# extension_board_v3.net
KiCad netlist of a schematic drawn in EAGLE
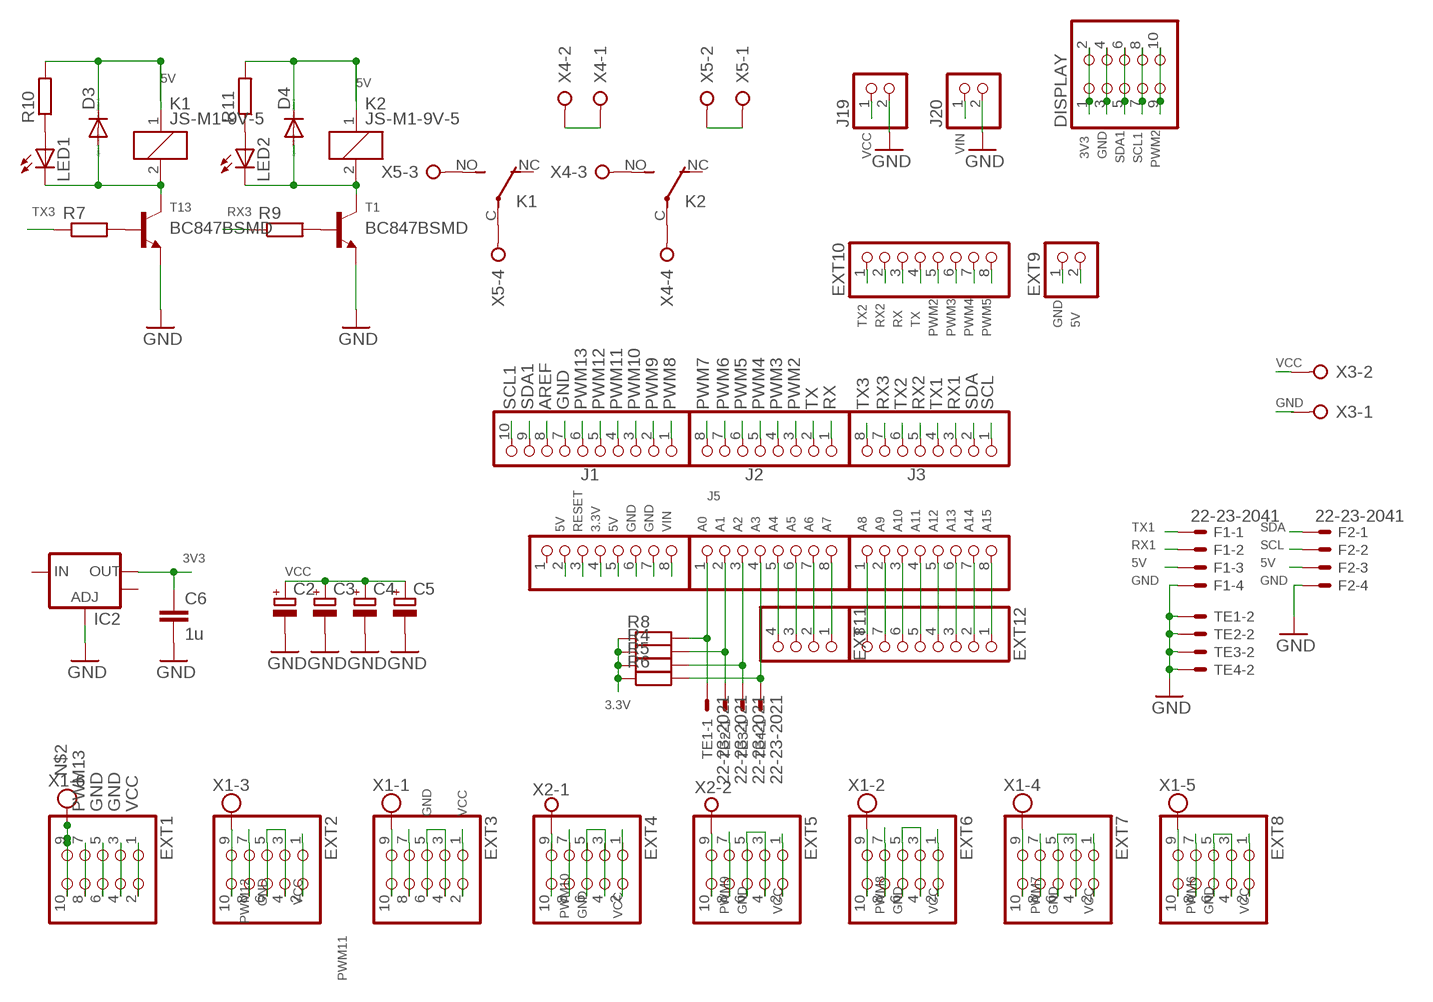
[diagram p0: schematic, sheet 1]

(export (version "E")
  (design (tool "Eeschema 10.0.6"))
  (components
    (comp (ref "C2")
      (value "CPOL-EUE2.5-7")
      (footprint "eagle-import:E2,5-7")
      (libsource (lib "eagle-import") (part "CPOL-EUE2.5-7"))
    )
    (comp (ref "C3")
      (value "CPOL-EUE2.5-7")
      (footprint "eagle-import:E2,5-7")
      (libsource (lib "eagle-import") (part "CPOL-EUE2.5-7"))
    )
    (comp (ref "C4")
      (value "CPOL-EUE2.5-7")
      (footprint "eagle-import:E2,5-7")
      (libsource (lib "eagle-import") (part "CPOL-EUE2.5-7"))
    )
    (comp (ref "C5")
      (value "CPOL-EUE2.5-7")
      (footprint "eagle-import:E2,5-7")
      (libsource (lib "eagle-import") (part "CPOL-EUE2.5-7"))
    )
    (comp (ref "C6")
      (value "1u")
      (footprint "eagle-import:C0805")
      (libsource (lib "eagle-import") (part "C-EUC0805"))
    )
    (comp (ref "D3")
      (value "DIODE-DO-214AC")
      (footprint "eagle-import:DO-214AC")
      (libsource (lib "eagle-import") (part "DIODE-DO-214AC"))
    )
    (comp (ref "D4")
      (value "DIODE-DO-214AC")
      (footprint "eagle-import:DO-214AC")
      (libsource (lib "eagle-import") (part "DIODE-DO-214AC"))
    )
    (comp (ref "DISPLAY")
      (value "PINHD-2X5")
      (footprint "eagle-import:2X05")
      (libsource (lib "eagle-import") (part "PINHD-2X5"))
    )
    (comp (ref "EXT1")
      (value "PINHD-2X5")
      (footprint "eagle-import:2X05")
      (libsource (lib "eagle-import") (part "PINHD-2X5"))
    )
    (comp (ref "EXT2")
      (value "PINHD-2X5")
      (footprint "eagle-import:2X05")
      (libsource (lib "eagle-import") (part "PINHD-2X5"))
    )
    (comp (ref "EXT3")
      (value "PINHD-2X5")
      (footprint "eagle-import:2X05")
      (libsource (lib "eagle-import") (part "PINHD-2X5"))
    )
    (comp (ref "EXT4")
      (value "PINHD-2X5")
      (footprint "eagle-import:2X05")
      (libsource (lib "eagle-import") (part "PINHD-2X5"))
    )
    (comp (ref "EXT5")
      (value "PINHD-2X5")
      (footprint "eagle-import:2X05")
      (libsource (lib "eagle-import") (part "PINHD-2X5"))
    )
    (comp (ref "EXT6")
      (value "PINHD-2X5")
      (footprint "eagle-import:2X05")
      (libsource (lib "eagle-import") (part "PINHD-2X5"))
    )
    (comp (ref "EXT7")
      (value "PINHD-2X5")
      (footprint "eagle-import:2X05")
      (libsource (lib "eagle-import") (part "PINHD-2X5"))
    )
    (comp (ref "EXT8")
      (value "PINHD-2X5")
      (footprint "eagle-import:2X05")
      (libsource (lib "eagle-import") (part "PINHD-2X5"))
    )
    (comp (ref "EXT9")
      (value "PINHD-1X2")
      (footprint "eagle-import:1X02")
      (libsource (lib "eagle-import") (part "PINHD-1X2"))
    )
    (comp (ref "EXT10")
      (value "PINHD-1X8")
      (footprint "eagle-import:1X08")
      (libsource (lib "eagle-import") (part "PINHD-1X8"))
    )
    (comp (ref "EXT11")
      (value "PINHD-1X4")
      (footprint "eagle-import:1X04")
      (libsource (lib "eagle-import") (part "PINHD-1X4"))
    )
    (comp (ref "EXT12")
      (value "PINHD-1X8")
      (footprint "eagle-import:1X08")
      (libsource (lib "eagle-import") (part "PINHD-1X8"))
    )
    (comp (ref "F1")
      (value "22-23-2041")
      (footprint "eagle-import:22-23-2041")
      (fields (field (name "MF") "MOLEX"))
      (libsource (lib "eagle-import") (part "22-23-2041"))
    )
    (comp (ref "F2")
      (value "22-23-2041")
      (footprint "eagle-import:22-23-2041")
      (fields (field (name "MF") "MOLEX"))
      (libsource (lib "eagle-import") (part "22-23-2041"))
    )
    (comp (ref "IC2")
      (value "V_REG_LM1117SOT223")
      (footprint "eagle-import:SOT223")
      (libsource (lib "eagle-import") (part "V_REG_LM1117SOT223"))
    )
    (comp (ref "J1")
      (value "PINHD-1X10")
      (footprint "eagle-import:1X10")
      (libsource (lib "eagle-import") (part "PINHD-1X10"))
    )
    (comp (ref "J2")
      (value "PINHD-1X8")
      (footprint "eagle-import:1X08")
      (libsource (lib "eagle-import") (part "PINHD-1X8"))
    )
    (comp (ref "J3")
      (value "PINHD-1X8")
      (footprint "eagle-import:1X08")
      (libsource (lib "eagle-import") (part "PINHD-1X8"))
    )
    (comp (ref "J4")
      (value "PINHD-1X8")
      (footprint "eagle-import:1X08")
      (libsource (lib "eagle-import") (part "PINHD-1X8"))
    )
    (comp (ref "J5")
      (value "PINHD-1X8")
      (footprint "eagle-import:1X08")
      (libsource (lib "eagle-import") (part "PINHD-1X8"))
    )
    (comp (ref "J6")
      (value "PINHD-1X8")
      (footprint "eagle-import:1X08")
      (libsource (lib "eagle-import") (part "PINHD-1X8"))
    )
    (comp (ref "J19")
      (value "PINHD-1X2")
      (footprint "eagle-import:1X02")
      (libsource (lib "eagle-import") (part "PINHD-1X2"))
    )
    (comp (ref "J20")
      (value "PINHD-1X2")
      (footprint "eagle-import:1X02")
      (libsource (lib "eagle-import") (part "PINHD-1X2"))
    )
    (comp (ref "K1")
      (value "JS-M1-9V-5")
      (footprint "eagle-import:JS-M")
      (libsource (lib "eagle-import") (part "JS-M1-9V-5"))
    )
    (comp (ref "K2")
      (value "JS-M1-9V-5")
      (footprint "eagle-import:JS-M")
      (libsource (lib "eagle-import") (part "JS-M1-9V-5"))
    )
    (comp (ref "LED1")
      (value "LEDSML1206")
      (footprint "eagle-import:SML1206")
      (libsource (lib "eagle-import") (part "LEDSML1206"))
    )
    (comp (ref "LED2")
      (value "LEDSML1206")
      (footprint "eagle-import:SML1206")
      (libsource (lib "eagle-import") (part "LEDSML1206"))
    )
    (comp (ref "R4")
      (value "R-EU_R1206")
      (footprint "eagle-import:R1206")
      (libsource (lib "eagle-import") (part "R-EU_R1206"))
    )
    (comp (ref "R5")
      (value "R-EU_R1206")
      (footprint "eagle-import:R1206")
      (libsource (lib "eagle-import") (part "R-EU_R1206"))
    )
    (comp (ref "R6")
      (value "R-EU_R1206")
      (footprint "eagle-import:R1206")
      (libsource (lib "eagle-import") (part "R-EU_R1206"))
    )
    (comp (ref "R7")
      (value "R-EU_R1206")
      (footprint "eagle-import:R1206")
      (libsource (lib "eagle-import") (part "R-EU_R1206"))
    )
    (comp (ref "R8")
      (value "R-EU_R1206")
      (footprint "eagle-import:R1206")
      (libsource (lib "eagle-import") (part "R-EU_R1206"))
    )
    (comp (ref "R9")
      (value "R-EU_R1206")
      (footprint "eagle-import:R1206")
      (libsource (lib "eagle-import") (part "R-EU_R1206"))
    )
    (comp (ref "R10")
      (value "R-EU_R1206")
      (footprint "eagle-import:R1206")
      (libsource (lib "eagle-import") (part "R-EU_R1206"))
    )
    (comp (ref "R11")
      (value "R-EU_R1206")
      (footprint "eagle-import:R1206")
      (libsource (lib "eagle-import") (part "R-EU_R1206"))
    )
    (comp (ref "T1")
      (value "BC847BSMD")
      (footprint "eagle-import:SOT23")
      (libsource (lib "eagle-import") (part "BC847SMDB"))
    )
    (comp (ref "T13")
      (value "BC847BSMD")
      (footprint "eagle-import:SOT23")
      (libsource (lib "eagle-import") (part "BC847SMDB"))
    )
    (comp (ref "TE1")
      (value "22-23-2021")
      (footprint "eagle-import:22-23-2021")
      (fields (field (name "MF") "MOLEX") (field (name "SPICEPREFIX") "X"))
      (libsource (lib "eagle-import") (part "22-23-2021"))
    )
    (comp (ref "TE2")
      (value "22-23-2021")
      (footprint "eagle-import:22-23-2021")
      (fields (field (name "MF") "MOLEX") (field (name "SPICEPREFIX") "X"))
      (libsource (lib "eagle-import") (part "22-23-2021"))
    )
    (comp (ref "TE3")
      (value "22-23-2021")
      (footprint "eagle-import:22-23-2021")
      (fields (field (name "MF") "MOLEX") (field (name "SPICEPREFIX") "X"))
      (libsource (lib "eagle-import") (part "22-23-2021"))
    )
    (comp (ref "TE4")
      (value "22-23-2021")
      (footprint "eagle-import:22-23-2021")
      (fields (field (name "MF") "MOLEX") (field (name "SPICEPREFIX") "X"))
      (libsource (lib "eagle-import") (part "22-23-2021"))
    )
    (comp (ref "X1")
      (value "W237-6")
      (footprint "eagle-import:W237-6")
      (libsource (lib "eagle-import") (part "W237-6"))
    )
    (comp (ref "X2")
      (value "W237-02P")
      (footprint "eagle-import:W237-132")
      (libsource (lib "eagle-import") (part "W237-02P"))
    )
    (comp (ref "X3")
      (value "W237-02P")
      (footprint "eagle-import:W237-132")
      (libsource (lib "eagle-import") (part "W237-02P"))
    )
    (comp (ref "X4")
      (value "W237-04P")
      (footprint "eagle-import:W237-4P")
      (libsource (lib "eagle-import") (part "W237-04P"))
    )
    (comp (ref "X5")
      (value "W237-04P")
      (footprint "eagle-import:W237-4P")
      (libsource (lib "eagle-import") (part "W237-04P"))
    )
  )
  (nets
    (net (code "1") (name "/3.3V") (class "Default")
      (node (ref "J6") (pin "4") (pinfunction "4_4") (pintype "passive"))
      (node (ref "R4") (pin "1") (pinfunction "1_1") (pintype "passive"))
      (node (ref "R5") (pin "1") (pinfunction "1_1") (pintype "passive"))
      (node (ref "R6") (pin "1") (pinfunction "1_1") (pintype "passive"))
      (node (ref "R8") (pin "1") (pinfunction "1_1") (pintype "passive"))
    )
    (net (code "2") (name "/3V3") (class "Default")
      (node (ref "C6") (pin "1") (pinfunction "1_1") (pintype "passive"))
      (node (ref "DISPLAY") (pin "1") (pinfunction "1_1") (pintype "passive"))
      (node (ref "DISPLAY") (pin "2") (pinfunction "2_2") (pintype "passive"))
      (node (ref "IC2") (pin "2") (pinfunction "OUT_2") (pintype "output"))
    )
    (net (code "3") (name "/5V") (class "Default")
      (node (ref "D3") (pin "C") (pinfunction "C_C") (pintype "passive"))
      (node (ref "D4") (pin "C") (pinfunction "C_C") (pintype "passive"))
      (node (ref "EXT9") (pin "2") (pinfunction "2_2") (pintype "passive"))
      (node (ref "F1") (pin "3") (pinfunction "S_3") (pintype "passive"))
      (node (ref "F2") (pin "3") (pinfunction "S_3") (pintype "passive"))
      (node (ref "J6") (pin "2") (pinfunction "2_2") (pintype "passive"))
      (node (ref "J6") (pin "5") (pinfunction "5_5") (pintype "passive"))
      (node (ref "K1") (pin "1") (pinfunction "1_1") (pintype "passive"))
      (node (ref "K2") (pin "1") (pinfunction "1_1") (pintype "passive"))
      (node (ref "R10") (pin "2") (pinfunction "2_2") (pintype "passive"))
      (node (ref "R11") (pin "2") (pinfunction "2_2") (pintype "passive"))
    )
    (net (code "4") (name "/A0") (class "Default")
      (node (ref "J5") (pin "1") (pinfunction "1_1") (pintype "passive"))
      (node (ref "R8") (pin "2") (pinfunction "2_2") (pintype "passive"))
      (node (ref "TE1") (pin "1") (pinfunction "S_1") (pintype "passive"))
    )
    (net (code "5") (name "/A1") (class "Default")
      (node (ref "J5") (pin "2") (pinfunction "2_2") (pintype "passive"))
      (node (ref "R4") (pin "2") (pinfunction "2_2") (pintype "passive"))
      (node (ref "TE2") (pin "1") (pinfunction "S_1") (pintype "passive"))
    )
    (net (code "6") (name "/A2") (class "Default")
      (node (ref "J5") (pin "3") (pinfunction "3_3") (pintype "passive"))
      (node (ref "R5") (pin "2") (pinfunction "2_2") (pintype "passive"))
      (node (ref "TE3") (pin "1") (pinfunction "S_1") (pintype "passive"))
    )
    (net (code "7") (name "/A3") (class "Default")
      (node (ref "J5") (pin "4") (pinfunction "4_4") (pintype "passive"))
      (node (ref "R6") (pin "2") (pinfunction "2_2") (pintype "passive"))
      (node (ref "TE4") (pin "1") (pinfunction "S_1") (pintype "passive"))
    )
    (net (code "8") (name "/A4") (class "Default")
      (node (ref "EXT11") (pin "4") (pinfunction "4_4") (pintype "passive"))
      (node (ref "J5") (pin "5") (pinfunction "5_5") (pintype "passive"))
    )
    (net (code "9") (name "/A5") (class "Default")
      (node (ref "EXT11") (pin "3") (pinfunction "3_3") (pintype "passive"))
      (node (ref "J5") (pin "6") (pinfunction "6_6") (pintype "passive"))
    )
    (net (code "10") (name "/A6") (class "Default")
      (node (ref "EXT11") (pin "2") (pinfunction "2_2") (pintype "passive"))
      (node (ref "J5") (pin "7") (pinfunction "7_7") (pintype "passive"))
    )
    (net (code "11") (name "/A7") (class "Default")
      (node (ref "EXT11") (pin "1") (pinfunction "1_1") (pintype "passive"))
      (node (ref "J5") (pin "8") (pinfunction "8_8") (pintype "passive"))
    )
    (net (code "12") (name "/A8") (class "Default")
      (node (ref "EXT12") (pin "8") (pinfunction "8_8") (pintype "passive"))
      (node (ref "J4") (pin "1") (pinfunction "1_1") (pintype "passive"))
    )
    (net (code "13") (name "/A9") (class "Default")
      (node (ref "EXT12") (pin "7") (pinfunction "7_7") (pintype "passive"))
      (node (ref "J4") (pin "2") (pinfunction "2_2") (pintype "passive"))
    )
    (net (code "14") (name "/A10") (class "Default")
      (node (ref "EXT12") (pin "6") (pinfunction "6_6") (pintype "passive"))
      (node (ref "J4") (pin "3") (pinfunction "3_3") (pintype "passive"))
    )
    (net (code "15") (name "/A11") (class "Default")
      (node (ref "EXT12") (pin "5") (pinfunction "5_5") (pintype "passive"))
      (node (ref "J4") (pin "4") (pinfunction "4_4") (pintype "passive"))
    )
    (net (code "16") (name "/A12") (class "Default")
      (node (ref "EXT12") (pin "4") (pinfunction "4_4") (pintype "passive"))
      (node (ref "J4") (pin "5") (pinfunction "5_5") (pintype "passive"))
    )
    (net (code "17") (name "/A13") (class "Default")
      (node (ref "EXT12") (pin "3") (pinfunction "3_3") (pintype "passive"))
      (node (ref "J4") (pin "6") (pinfunction "6_6") (pintype "passive"))
    )
    (net (code "18") (name "/A14") (class "Default")
      (node (ref "EXT12") (pin "2") (pinfunction "2_2") (pintype "passive"))
      (node (ref "J4") (pin "7") (pinfunction "7_7") (pintype "passive"))
    )
    (net (code "19") (name "/A15") (class "Default")
      (node (ref "EXT12") (pin "1") (pinfunction "1_1") (pintype "passive"))
      (node (ref "J4") (pin "8") (pinfunction "8_8") (pintype "passive"))
    )
    (net (code "20") (name "/AREF") (class "Default")
      (node (ref "J1") (pin "8") (pinfunction "8_8") (pintype "passive"))
    )
    (net (code "21") (name "/N$2") (class "Default")
      (node (ref "EXT1") (pin "10") (pinfunction "10_10") (pintype "passive"))
      (node (ref "EXT1") (pin "9") (pinfunction "9_9") (pintype "passive"))
      (node (ref "X1") (pin "6") (pinfunction "KL_6") (pintype "passive"))
    )
    (net (code "22") (name "/PWM2") (class "Default")
      (node (ref "DISPLAY") (pin "10") (pinfunction "10_10") (pintype "passive"))
      (node (ref "DISPLAY") (pin "9") (pinfunction "9_9") (pintype "passive"))
      (node (ref "EXT10") (pin "5") (pinfunction "5_5") (pintype "passive"))
      (node (ref "J2") (pin "3") (pinfunction "3_3") (pintype "passive"))
    )
    (net (code "23") (name "/PWM3") (class "Default")
      (node (ref "EXT10") (pin "6") (pinfunction "6_6") (pintype "passive"))
      (node (ref "J2") (pin "4") (pinfunction "4_4") (pintype "passive"))
    )
    (net (code "24") (name "/PWM4") (class "Default")
      (node (ref "EXT10") (pin "7") (pinfunction "7_7") (pintype "passive"))
      (node (ref "J2") (pin "5") (pinfunction "5_5") (pintype "passive"))
    )
    (net (code "25") (name "/PWM5") (class "Default")
      (node (ref "EXT10") (pin "8") (pinfunction "8_8") (pintype "passive"))
      (node (ref "J2") (pin "6") (pinfunction "6_6") (pintype "passive"))
    )
    (net (code "26") (name "/PWM6") (class "Default")
      (node (ref "EXT8") (pin "7") (pinfunction "7_7") (pintype "passive"))
      (node (ref "EXT8") (pin "8") (pinfunction "8_8") (pintype "passive"))
      (node (ref "J2") (pin "7") (pinfunction "7_7") (pintype "passive"))
    )
    (net (code "27") (name "/PWM7") (class "Default")
      (node (ref "EXT7") (pin "7") (pinfunction "7_7") (pintype "passive"))
      (node (ref "EXT7") (pin "8") (pinfunction "8_8") (pintype "passive"))
      (node (ref "J2") (pin "8") (pinfunction "8_8") (pintype "passive"))
    )
    (net (code "28") (name "/PWM8") (class "Default")
      (node (ref "EXT6") (pin "7") (pinfunction "7_7") (pintype "passive"))
      (node (ref "EXT6") (pin "8") (pinfunction "8_8") (pintype "passive"))
      (node (ref "J1") (pin "1") (pinfunction "1_1") (pintype "passive"))
    )
    (net (code "29") (name "/PWM9") (class "Default")
      (node (ref "EXT5") (pin "7") (pinfunction "7_7") (pintype "passive"))
      (node (ref "EXT5") (pin "8") (pinfunction "8_8") (pintype "passive"))
      (node (ref "J1") (pin "2") (pinfunction "2_2") (pintype "passive"))
    )
    (net (code "30") (name "/PWM10") (class "Default")
      (node (ref "EXT4") (pin "7") (pinfunction "7_7") (pintype "passive"))
      (node (ref "EXT4") (pin "8") (pinfunction "8_8") (pintype "passive"))
      (node (ref "J1") (pin "3") (pinfunction "3_3") (pintype "passive"))
    )
    (net (code "31") (name "/PWM11") (class "Default")
      (node (ref "EXT3") (pin "7") (pinfunction "7_7") (pintype "passive"))
      (node (ref "EXT3") (pin "8") (pinfunction "8_8") (pintype "passive"))
      (node (ref "J1") (pin "4") (pinfunction "4_4") (pintype "passive"))
    )
    (net (code "32") (name "/PWM12") (class "Default")
      (node (ref "EXT2") (pin "7") (pinfunction "7_7") (pintype "passive"))
      (node (ref "EXT2") (pin "8") (pinfunction "8_8") (pintype "passive"))
      (node (ref "J1") (pin "5") (pinfunction "5_5") (pintype "passive"))
    )
    (net (code "33") (name "/PWM13") (class "Default")
      (node (ref "EXT1") (pin "7") (pinfunction "7_7") (pintype "passive"))
      (node (ref "EXT1") (pin "8") (pinfunction "8_8") (pintype "passive"))
      (node (ref "J1") (pin "6") (pinfunction "6_6") (pintype "passive"))
    )
    (net (code "34") (name "/RESET") (class "Default")
      (node (ref "J6") (pin "3") (pinfunction "3_3") (pintype "passive"))
    )
    (net (code "35") (name "/RX") (class "Default")
      (node (ref "EXT10") (pin "3") (pinfunction "3_3") (pintype "passive"))
      (node (ref "J2") (pin "1") (pinfunction "1_1") (pintype "passive"))
    )
    (net (code "36") (name "/RX1") (class "Default")
      (node (ref "F1") (pin "2") (pinfunction "S_2") (pintype "passive"))
      (node (ref "J3") (pin "3") (pinfunction "3_3") (pintype "passive"))
    )
    (net (code "37") (name "/RX2") (class "Default")
      (node (ref "EXT10") (pin "2") (pinfunction "2_2") (pintype "passive"))
      (node (ref "J3") (pin "5") (pinfunction "5_5") (pintype "passive"))
    )
    (net (code "38") (name "/RX3") (class "Default")
      (node (ref "J3") (pin "7") (pinfunction "7_7") (pintype "passive"))
      (node (ref "R9") (pin "1") (pinfunction "1_1") (pintype "passive"))
    )
    (net (code "39") (name "/SCL") (class "Default")
      (node (ref "F2") (pin "2") (pinfunction "S_2") (pintype "passive"))
      (node (ref "J3") (pin "1") (pinfunction "1_1") (pintype "passive"))
    )
    (net (code "40") (name "/SCL1") (class "Default")
      (node (ref "DISPLAY") (pin "7") (pinfunction "7_7") (pintype "passive"))
      (node (ref "DISPLAY") (pin "8") (pinfunction "8_8") (pintype "passive"))
      (node (ref "J1") (pin "10") (pinfunction "10_10") (pintype "passive"))
    )
    (net (code "41") (name "/SDA") (class "Default")
      (node (ref "F2") (pin "1") (pinfunction "S_1") (pintype "passive"))
      (node (ref "J3") (pin "2") (pinfunction "2_2") (pintype "passive"))
    )
    (net (code "42") (name "/SDA1") (class "Default")
      (node (ref "DISPLAY") (pin "5") (pinfunction "5_5") (pintype "passive"))
      (node (ref "DISPLAY") (pin "6") (pinfunction "6_6") (pintype "passive"))
      (node (ref "J1") (pin "9") (pinfunction "9_9") (pintype "passive"))
    )
    (net (code "43") (name "/TX") (class "Default")
      (node (ref "EXT10") (pin "4") (pinfunction "4_4") (pintype "passive"))
      (node (ref "J2") (pin "2") (pinfunction "2_2") (pintype "passive"))
    )
    (net (code "44") (name "/TX1") (class "Default")
      (node (ref "F1") (pin "1") (pinfunction "S_1") (pintype "passive"))
      (node (ref "J3") (pin "4") (pinfunction "4_4") (pintype "passive"))
    )
    (net (code "45") (name "/TX2") (class "Default")
      (node (ref "EXT10") (pin "1") (pinfunction "1_1") (pintype "passive"))
      (node (ref "J3") (pin "6") (pinfunction "6_6") (pintype "passive"))
    )
    (net (code "46") (name "/TX3") (class "Default")
      (node (ref "J3") (pin "8") (pinfunction "8_8") (pintype "passive"))
      (node (ref "R7") (pin "1") (pinfunction "1_1") (pintype "passive"))
    )
    (net (code "47") (name "/VCC") (class "Default")
      (node (ref "C2") (pin "+") (pinfunction "+_+") (pintype "passive"))
      (node (ref "C3") (pin "+") (pinfunction "+_+") (pintype "passive"))
      (node (ref "C4") (pin "+") (pinfunction "+_+") (pintype "passive"))
      (node (ref "C5") (pin "+") (pinfunction "+_+") (pintype "passive"))
      (node (ref "EXT1") (pin "1") (pinfunction "1_1") (pintype "passive"))
      (node (ref "EXT1") (pin "2") (pinfunction "2_2") (pintype "passive"))
      (node (ref "EXT2") (pin "1") (pinfunction "1_1") (pintype "passive"))
      (node (ref "EXT2") (pin "2") (pinfunction "2_2") (pintype "passive"))
      (node (ref "EXT3") (pin "1") (pinfunction "1_1") (pintype "passive"))
      (node (ref "EXT3") (pin "2") (pinfunction "2_2") (pintype "passive"))
      (node (ref "EXT4") (pin "1") (pinfunction "1_1") (pintype "passive"))
      (node (ref "EXT4") (pin "2") (pinfunction "2_2") (pintype "passive"))
      (node (ref "EXT5") (pin "1") (pinfunction "1_1") (pintype "passive"))
      (node (ref "EXT5") (pin "2") (pinfunction "2_2") (pintype "passive"))
      (node (ref "EXT6") (pin "1") (pinfunction "1_1") (pintype "passive"))
      (node (ref "EXT6") (pin "2") (pinfunction "2_2") (pintype "passive"))
      (node (ref "EXT7") (pin "1") (pinfunction "1_1") (pintype "passive"))
      (node (ref "EXT7") (pin "2") (pinfunction "2_2") (pintype "passive"))
      (node (ref "EXT8") (pin "1") (pinfunction "1_1") (pintype "passive"))
      (node (ref "EXT8") (pin "2") (pinfunction "2_2") (pintype "passive"))
      (node (ref "J19") (pin "1") (pinfunction "1_1") (pintype "passive"))
      (node (ref "X3") (pin "2") (pinfunction "KL_2") (pintype "passive"))
    )
    (net (code "48") (name "/VIN") (class "Default")
      (node (ref "J20") (pin "1") (pinfunction "1_1") (pintype "passive"))
      (node (ref "J6") (pin "8") (pinfunction "8_8") (pintype "passive"))
    )
    (net (code "49") (name "GND") (class "Default")
      (node (ref "C2") (pin "-") (pinfunction "-_-") (pintype "passive"))
      (node (ref "C3") (pin "-") (pinfunction "-_-") (pintype "passive"))
      (node (ref "C4") (pin "-") (pinfunction "-_-") (pintype "passive"))
      (node (ref "C5") (pin "-") (pinfunction "-_-") (pintype "passive"))
      (node (ref "C6") (pin "2") (pinfunction "2_2") (pintype "passive"))
      (node (ref "DISPLAY") (pin "3") (pinfunction "3_3") (pintype "passive"))
      (node (ref "DISPLAY") (pin "4") (pinfunction "4_4") (pintype "passive"))
      (node (ref "EXT1") (pin "3") (pinfunction "3_3") (pintype "passive"))
      (node (ref "EXT1") (pin "4") (pinfunction "4_4") (pintype "passive"))
      (node (ref "EXT1") (pin "5") (pinfunction "5_5") (pintype "passive"))
      (node (ref "EXT1") (pin "6") (pinfunction "6_6") (pintype "passive"))
      (node (ref "EXT2") (pin "3") (pinfunction "3_3") (pintype "passive"))
      (node (ref "EXT2") (pin "4") (pinfunction "4_4") (pintype "passive"))
      (node (ref "EXT2") (pin "5") (pinfunction "5_5") (pintype "passive"))
      (node (ref "EXT2") (pin "6") (pinfunction "6_6") (pintype "passive"))
      (node (ref "EXT3") (pin "3") (pinfunction "3_3") (pintype "passive"))
      (node (ref "EXT3") (pin "4") (pinfunction "4_4") (pintype "passive"))
      (node (ref "EXT3") (pin "5") (pinfunction "5_5") (pintype "passive"))
      (node (ref "EXT3") (pin "6") (pinfunction "6_6") (pintype "passive"))
      (node (ref "EXT4") (pin "3") (pinfunction "3_3") (pintype "passive"))
      (node (ref "EXT4") (pin "4") (pinfunction "4_4") (pintype "passive"))
      (node (ref "EXT4") (pin "5") (pinfunction "5_5") (pintype "passive"))
      (node (ref "EXT4") (pin "6") (pinfunction "6_6") (pintype "passive"))
      (node (ref "EXT5") (pin "3") (pinfunction "3_3") (pintype "passive"))
      (node (ref "EXT5") (pin "4") (pinfunction "4_4") (pintype "passive"))
      (node (ref "EXT5") (pin "5") (pinfunction "5_5") (pintype "passive"))
      (node (ref "EXT5") (pin "6") (pinfunction "6_6") (pintype "passive"))
      (node (ref "EXT6") (pin "3") (pinfunction "3_3") (pintype "passive"))
      (node (ref "EXT6") (pin "4") (pinfunction "4_4") (pintype "passive"))
      (node (ref "EXT6") (pin "5") (pinfunction "5_5") (pintype "passive"))
      (node (ref "EXT6") (pin "6") (pinfunction "6_6") (pintype "passive"))
      (node (ref "EXT7") (pin "3") (pinfunction "3_3") (pintype "passive"))
      (node (ref "EXT7") (pin "4") (pinfunction "4_4") (pintype "passive"))
      (node (ref "EXT7") (pin "5") (pinfunction "5_5") (pintype "passive"))
      (node (ref "EXT7") (pin "6") (pinfunction "6_6") (pintype "passive"))
      (node (ref "EXT8") (pin "3") (pinfunction "3_3") (pintype "passive"))
      (node (ref "EXT8") (pin "4") (pinfunction "4_4") (pintype "passive"))
      (node (ref "EXT8") (pin "5") (pinfunction "5_5") (pintype "passive"))
      (node (ref "EXT8") (pin "6") (pinfunction "6_6") (pintype "passive"))
      (node (ref "EXT9") (pin "1") (pinfunction "1_1") (pintype "passive"))
      (node (ref "F1") (pin "4") (pinfunction "S_4") (pintype "passive"))
      (node (ref "F2") (pin "4") (pinfunction "S_4") (pintype "passive"))
      (node (ref "IC2") (pin "1") (pinfunction "ADJ_1") (pintype "input"))
      (node (ref "J1") (pin "7") (pinfunction "7_7") (pintype "passive"))
      (node (ref "J19") (pin "2") (pinfunction "2_2") (pintype "passive"))
      (node (ref "J20") (pin "2") (pinfunction "2_2") (pintype "passive"))
      (node (ref "J6") (pin "6") (pinfunction "6_6") (pintype "passive"))
      (node (ref "J6") (pin "7") (pinfunction "7_7") (pintype "passive"))
      (node (ref "T1") (pin "2") (pinfunction "E_2") (pintype "passive"))
      (node (ref "T13") (pin "2") (pinfunction "E_2") (pintype "passive"))
      (node (ref "TE1") (pin "2") (pinfunction "S_2") (pintype "passive"))
      (node (ref "TE2") (pin "2") (pinfunction "S_2") (pintype "passive"))
      (node (ref "TE3") (pin "2") (pinfunction "S_2") (pintype "passive"))
      (node (ref "TE4") (pin "2") (pinfunction "S_2") (pintype "passive"))
      (node (ref "X3") (pin "1") (pinfunction "KL_1") (pintype "passive"))
    )
    (net (code "50") (name "Net-(K1B-P)") (class "Default")
      (node (ref "K1") (pin "C") (pinfunction "P_C") (pintype "passive"))
      (node (ref "X5") (pin "4") (pinfunction "KL_4") (pintype "passive"))
    )
    (net (code "51") (name "Net-(K1B-S)") (class "Default")
      (node (ref "K1") (pin "NO") (pinfunction "S_NO") (pintype "passive"))
      (node (ref "X5") (pin "3") (pinfunction "KL_3") (pintype "passive"))
    )
    (net (code "52") (name "Net-(K2B-P)") (class "Default")
      (node (ref "K2") (pin "C") (pinfunction "P_C") (pintype "passive"))
      (node (ref "X4") (pin "4") (pinfunction "KL_4") (pintype "passive"))
    )
    (net (code "53") (name "Net-(K2B-S)") (class "Default")
      (node (ref "K2") (pin "NO") (pinfunction "S_NO") (pintype "passive"))
      (node (ref "X4") (pin "3") (pinfunction "KL_3") (pintype "passive"))
    )
    (net (code "54") (name "Net-(LED1-PadA)") (class "Default")
      (node (ref "LED1") (pin "A") (pinfunction "A_A") (pintype "passive"))
      (node (ref "R10") (pin "1") (pinfunction "1_1") (pintype "passive"))
    )
    (net (code "55") (name "Net-(LED2-PadA)") (class "Default")
      (node (ref "LED2") (pin "A") (pinfunction "A_A") (pintype "passive"))
      (node (ref "R11") (pin "1") (pinfunction "1_1") (pintype "passive"))
    )
    (net (code "56") (name "Net-(T1-B)") (class "Default")
      (node (ref "R9") (pin "2") (pinfunction "2_2") (pintype "passive"))
      (node (ref "T1") (pin "1") (pinfunction "B_1") (pintype "passive"))
    )
    (net (code "57") (name "Net-(T1-C)") (class "Default")
      (node (ref "D4") (pin "A") (pinfunction "A_A") (pintype "passive"))
      (node (ref "K2") (pin "2") (pinfunction "2_2") (pintype "passive"))
      (node (ref "LED2") (pin "C") (pinfunction "C_C") (pintype "passive"))
      (node (ref "T1") (pin "3") (pinfunction "C_3") (pintype "passive"))
    )
    (net (code "58") (name "Net-(T13-B)") (class "Default")
      (node (ref "R7") (pin "2") (pinfunction "2_2") (pintype "passive"))
      (node (ref "T13") (pin "1") (pinfunction "B_1") (pintype "passive"))
    )
    (net (code "59") (name "Net-(T13-C)") (class "Default")
      (node (ref "D3") (pin "A") (pinfunction "A_A") (pintype "passive"))
      (node (ref "K1") (pin "2") (pinfunction "2_2") (pintype "passive"))
      (node (ref "LED1") (pin "C") (pinfunction "C_C") (pintype "passive"))
      (node (ref "T13") (pin "3") (pinfunction "C_3") (pintype "passive"))
    )
    (net (code "60") (name "Net-(X1A-KL)") (class "Default")
      (node (ref "EXT3") (pin "10") (pinfunction "10_10") (pintype "passive"))
      (node (ref "EXT3") (pin "9") (pinfunction "9_9") (pintype "passive"))
      (node (ref "X1") (pin "1") (pinfunction "KL_1") (pintype "passive"))
    )
    (net (code "61") (name "Net-(X1B-KL)") (class "Default")
      (node (ref "EXT6") (pin "10") (pinfunction "10_10") (pintype "passive"))
      (node (ref "EXT6") (pin "9") (pinfunction "9_9") (pintype "passive"))
      (node (ref "X1") (pin "2") (pinfunction "KL_2") (pintype "passive"))
    )
    (net (code "62") (name "Net-(X1C-KL)") (class "Default")
      (node (ref "EXT2") (pin "10") (pinfunction "10_10") (pintype "passive"))
      (node (ref "EXT2") (pin "9") (pinfunction "9_9") (pintype "passive"))
      (node (ref "X1") (pin "3") (pinfunction "KL_3") (pintype "passive"))
    )
    (net (code "63") (name "Net-(X1D-KL)") (class "Default")
      (node (ref "EXT7") (pin "10") (pinfunction "10_10") (pintype "passive"))
      (node (ref "EXT7") (pin "9") (pinfunction "9_9") (pintype "passive"))
      (node (ref "X1") (pin "4") (pinfunction "KL_4") (pintype "passive"))
    )
    (net (code "64") (name "Net-(X1E-KL)") (class "Default")
      (node (ref "EXT8") (pin "10") (pinfunction "10_10") (pintype "passive"))
      (node (ref "EXT8") (pin "9") (pinfunction "9_9") (pintype "passive"))
      (node (ref "X1") (pin "5") (pinfunction "KL_5") (pintype "passive"))
    )
    (net (code "65") (name "Net-(X2A-KL)") (class "Default")
      (node (ref "EXT4") (pin "10") (pinfunction "10_10") (pintype "passive"))
      (node (ref "EXT4") (pin "9") (pinfunction "9_9") (pintype "passive"))
      (node (ref "X2") (pin "1") (pinfunction "KL_1") (pintype "passive"))
    )
    (net (code "66") (name "Net-(X2B-KL)") (class "Default")
      (node (ref "EXT5") (pin "10") (pinfunction "10_10") (pintype "passive"))
      (node (ref "EXT5") (pin "9") (pinfunction "9_9") (pintype "passive"))
      (node (ref "X2") (pin "2") (pinfunction "KL_2") (pintype "passive"))
    )
    (net (code "67") (name "Net-(X4A-KL)") (class "Default")
      (node (ref "X4") (pin "1") (pinfunction "KL_1") (pintype "passive"))
      (node (ref "X4") (pin "2") (pinfunction "KL_2") (pintype "passive"))
    )
    (net (code "68") (name "Net-(X5A-KL)") (class "Default")
      (node (ref "X5") (pin "1") (pinfunction "KL_1") (pintype "passive"))
      (node (ref "X5") (pin "2") (pinfunction "KL_2") (pintype "passive"))
    )
    (net (code "69") (name "unconnected-(IC2-IN-Pad3)") (class "Default")
      (node (ref "IC2") (pin "3") (pinfunction "IN_3") (pintype "input"))
    )
    (net (code "70") (name "unconnected-(IC2-OUT-Pad4)") (class "Default")
      (node (ref "IC2") (pin "4") (pinfunction "OUT_4") (pintype "output"))
    )
    (net (code "71") (name "unconnected-(J6-Pad1)") (class "Default")
      (node (ref "J6") (pin "1") (pinfunction "1_1") (pintype "passive"))
    )
    (net (code "72") (name "unconnected-(K1B-O-PadNC)") (class "Default")
      (node (ref "K1") (pin "NC") (pinfunction "O_NC") (pintype "passive"))
    )
    (net (code "73") (name "unconnected-(K2B-O-PadNC)") (class "Default")
      (node (ref "K2") (pin "NC") (pinfunction "O_NC") (pintype "passive"))
    )
  )
)
